# tracker2.net
KiCad netlist of a schematic drawn in EAGLE
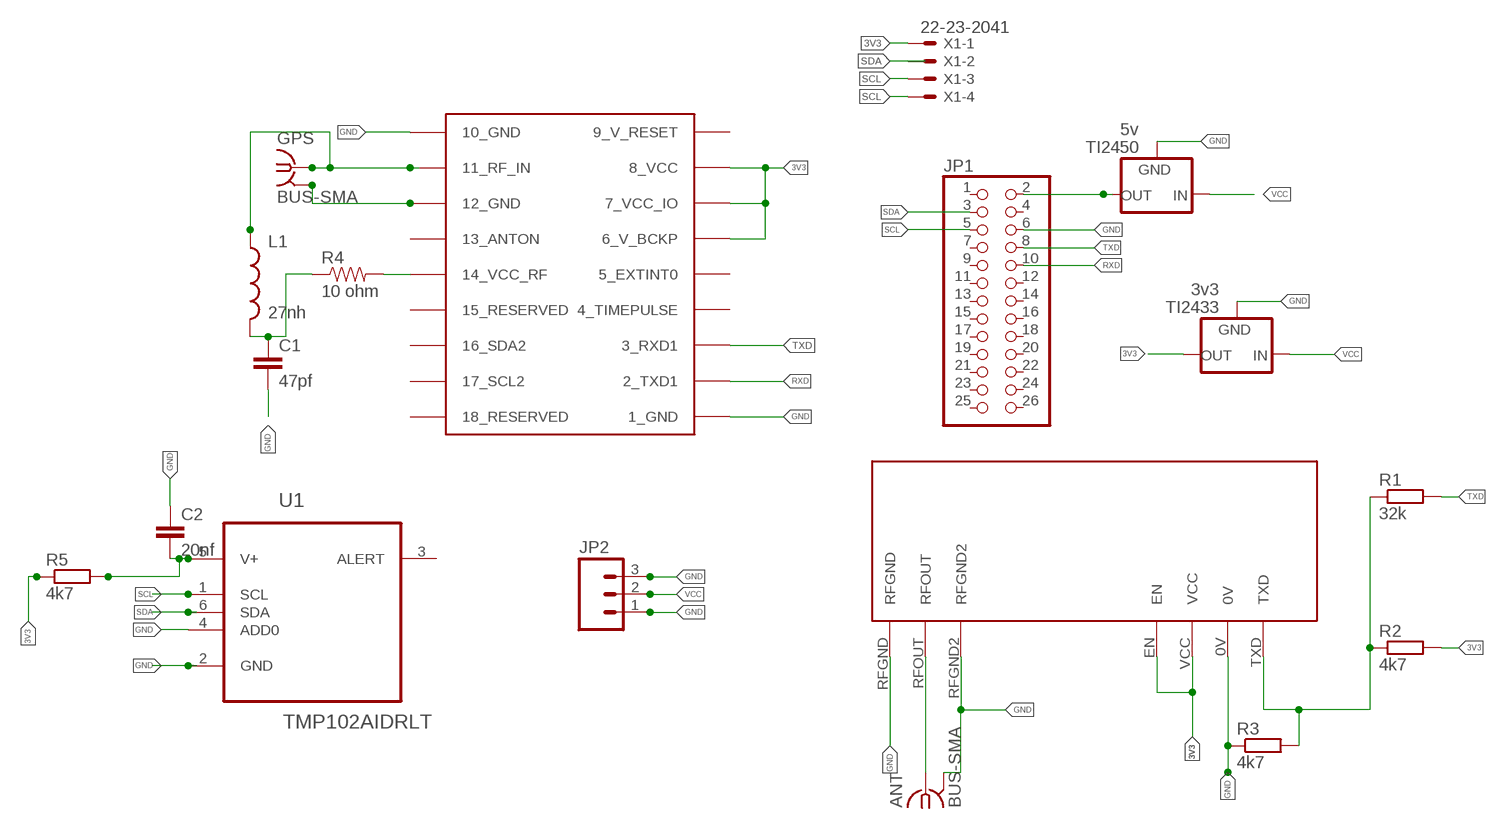
[diagram p0: schematic, sheet 1]

(export (version "E")
  (design (tool "Eeschema 10.0.6"))
  (components
    (comp (ref "ANT")
      (value "BUS-SMA")
      (footprint "eagle-import:BUS-SMA")
      (libsource (lib "eagle-import") (part "BUS-SMA"))
    )
    (comp (ref "C1")
      (value "47pf")
      (footprint "eagle-import:0603-CAP")
      (libsource (lib "eagle-import") (part "CAP0603-CAP"))
    )
    (comp (ref "C2")
      (value "20nf")
      (footprint "eagle-import:C0603")
      (libsource (lib "eagle-import") (part "C-EUC0603"))
    )
    (comp (ref "GPS")
      (value "BUS-SMA")
      (footprint "eagle-import:BUS-SMA")
      (libsource (lib "eagle-import") (part "BUS-SMA"))
    )
    (comp (ref "JP1")
      (value "PINHD-2X13")
      (footprint "eagle-import:2X13")
      (libsource (lib "eagle-import") (part "PINHD-2X13"))
    )
    (comp (ref "JP2")
      (value "M03PTH")
      (footprint "eagle-import:1X03")
      (libsource (lib "eagle-import") (part "M03PTH"))
    )
    (comp (ref "L1")
      (value "27nh")
      (footprint "eagle-import:0603")
      (libsource (lib "eagle-import") (part "INDUCTOR0603"))
    )
    (comp (ref "R1")
      (value "32k")
      (footprint "eagle-import:R0603")
      (libsource (lib "eagle-import") (part "R-EU_R0603"))
    )
    (comp (ref "R2")
      (value "4k7")
      (footprint "eagle-import:R0603")
      (libsource (lib "eagle-import") (part "R-EU_R0603"))
    )
    (comp (ref "R3")
      (value "4k7")
      (footprint "eagle-import:R0603")
      (libsource (lib "eagle-import") (part "R-EU_R0603"))
    )
    (comp (ref "R4")
      (value "10 ohm")
      (footprint "eagle-import:0603-RES")
      (libsource (lib "eagle-import") (part "RESISTOR0603"))
    )
    (comp (ref "R5")
      (value "4k7")
      (footprint "eagle-import:R0603")
      (libsource (lib "eagle-import") (part "R-EU_R0603"))
    )
    (comp (ref "TI2433")
      (value "3v3")
      (footprint "eagle-import:TO-220-ALT")
      (libsource (lib "eagle-import") (part "V_REG_78XX-TO-220"))
    )
    (comp (ref "TI2450")
      (value "5v")
      (footprint "eagle-import:TO-220-ALT")
      (libsource (lib "eagle-import") (part "V_REG_78XX-TO-220"))
    )
    (comp (ref "U$1")
      (value "NTX2")
      (footprint "eagle-import:NTX2")
      (libsource (lib "eagle-import") (part "NTX2"))
    )
    (comp (ref "U$2")
      (value "UBLOX_MAX")
      (footprint "eagle-import:UBLOX_MAX")
      (libsource (lib "eagle-import") (part "UBLOX_MAX"))
    )
    (comp (ref "U1")
      (value "TMP102AIDRLT")
      (footprint "eagle-import:SOT50P160X60-6N")
      (libsource (lib "eagle-import") (part "TMP102AIDRLT"))
    )
    (comp (ref "X1")
      (value "22-23-2041")
      (footprint "eagle-import:22-23-2041")
      (fields (field (name "MF") "MOLEX"))
      (libsource (lib "eagle-import") (part "22-23-2041"))
    )
  )
  (nets
    (net (code "1") (name "/9_V_RESET") (class "Default")
      (node (ref "U$2") (pin "9_V_RESET") (pinfunction "9_V_RESET_9_V_RESET") (pintype "power_in"))
    )
    (net (code "2") (name "3V3") (class "Default")
      (node (ref "C2") (pin "2") (pinfunction "2_2") (pintype "passive"))
      (node (ref "R2") (pin "2") (pinfunction "2_2") (pintype "passive"))
      (node (ref "R5") (pin "1") (pinfunction "1_1") (pintype "passive"))
      (node (ref "R5") (pin "2") (pinfunction "2_2") (pintype "passive"))
      (node (ref "TI2433") (pin "OUT") (pinfunction "OUT_OUT") (pintype "output"))
      (node (ref "U$1") (pin "EN") (pinfunction "EN_EN") (pintype "bidirectional"))
      (node (ref "U$1") (pin "VCC") (pinfunction "VCC_VCC") (pintype "bidirectional"))
      (node (ref "U$2") (pin "6_V_BCKP") (pinfunction "6_V_BCKP_6_V_BCKP") (pintype "bidirectional"))
      (node (ref "U$2") (pin "7_VCC_IO") (pinfunction "7_VCC_IO_7_VCC_IO") (pintype "power_in"))
      (node (ref "U$2") (pin "8_VCC") (pinfunction "8_VCC_8_VCC") (pintype "power_in"))
      (node (ref "U1") (pin "5") (pinfunction "V+_5") (pintype "power_in"))
      (node (ref "X1") (pin "1") (pinfunction "S_1") (pintype "passive"))
    )
    (net (code "3") (name "GND") (class "Default")
      (node (ref "ANT") (pin "2") (pinfunction "GND_2") (pintype "power_in"))
      (node (ref "ANT") (pin "3") (pinfunction "GND_3") (pintype "power_in"))
      (node (ref "ANT") (pin "4") (pinfunction "GND_4") (pintype "power_in"))
      (node (ref "ANT") (pin "5") (pinfunction "GND_5") (pintype "power_in"))
      (node (ref "C1") (pin "2") (pinfunction "2_2") (pintype "passive"))
      (node (ref "C2") (pin "1") (pinfunction "1_1") (pintype "passive"))
      (node (ref "GPS") (pin "2") (pinfunction "GND_2") (pintype "power_in"))
      (node (ref "GPS") (pin "3") (pinfunction "GND_3") (pintype "power_in"))
      (node (ref "GPS") (pin "4") (pinfunction "GND_4") (pintype "power_in"))
      (node (ref "GPS") (pin "5") (pinfunction "GND_5") (pintype "power_in"))
      (node (ref "JP1") (pin "6") (pinfunction "6_6") (pintype "passive"))
      (node (ref "JP2") (pin "1") (pinfunction "1_1") (pintype "passive"))
      (node (ref "JP2") (pin "3") (pinfunction "3_3") (pintype "passive"))
      (node (ref "R3") (pin "1") (pinfunction "1_1") (pintype "passive"))
      (node (ref "TI2433") (pin "GND") (pinfunction "GND_GND") (pintype "input"))
      (node (ref "TI2450") (pin "GND") (pinfunction "GND_GND") (pintype "input"))
      (node (ref "U$1") (pin "0V") (pinfunction "0V_0V") (pintype "bidirectional"))
      (node (ref "U$1") (pin "RFGND") (pinfunction "RFGND_RFGND") (pintype "bidirectional"))
      (node (ref "U$1") (pin "RFGND2") (pinfunction "RFGND2_RFGND2") (pintype "bidirectional"))
      (node (ref "U$2") (pin "10_GND") (pinfunction "10_GND_10_GND") (pintype "power_in"))
      (node (ref "U$2") (pin "12_GND") (pinfunction "12_GND_12_GND") (pintype "power_in"))
      (node (ref "U$2") (pin "1_GND") (pinfunction "1_GND_1_GND") (pintype "power_in"))
      (node (ref "U1") (pin "2") (pinfunction "GND_2") (pintype "passive"))
      (node (ref "U1") (pin "4") (pinfunction "ADD0_4") (pintype "input"))
      (node (ref "X1") (pin "4") (pinfunction "S_4") (pintype "passive"))
    )
    (net (code "4") (name "Net-(ANT-Pad1)") (class "Default")
      (node (ref "ANT") (pin "1") (pinfunction "1_1") (pintype "passive"))
      (node (ref "U$1") (pin "RFOUT") (pinfunction "RFOUT_RFOUT") (pintype "bidirectional"))
    )
    (net (code "5") (name "Net-(C1-Pad1)") (class "Default")
      (node (ref "C1") (pin "1") (pinfunction "1_1") (pintype "passive"))
      (node (ref "L1") (pin "2") (pinfunction "2_2") (pintype "passive"))
      (node (ref "R4") (pin "1") (pinfunction "1_1") (pintype "passive"))
    )
    (net (code "6") (name "Net-(GPS-Pad1)") (class "Default")
      (node (ref "GPS") (pin "1") (pinfunction "1_1") (pintype "passive"))
      (node (ref "L1") (pin "1") (pinfunction "1_1") (pintype "passive"))
      (node (ref "U$2") (pin "11_RF_IN") (pinfunction "11_RF_IN_11_RF_IN") (pintype "bidirectional"))
    )
    (net (code "7") (name "Net-(JP1-Pad2)") (class "Default")
      (node (ref "JP1") (pin "2") (pinfunction "2_2") (pintype "passive"))
      (node (ref "TI2450") (pin "OUT") (pinfunction "OUT_OUT") (pintype "output"))
    )
    (net (code "8") (name "Net-(R1-Pad1)") (class "Default")
      (node (ref "R1") (pin "1") (pinfunction "1_1") (pintype "passive"))
      (node (ref "R2") (pin "1") (pinfunction "1_1") (pintype "passive"))
      (node (ref "R3") (pin "2") (pinfunction "2_2") (pintype "passive"))
      (node (ref "U$1") (pin "TXD") (pinfunction "TXD_TXD") (pintype "bidirectional"))
    )
    (net (code "9") (name "Net-(R4-Pad2)") (class "Default")
      (node (ref "R4") (pin "2") (pinfunction "2_2") (pintype "passive"))
      (node (ref "U$2") (pin "14_VCC_RF") (pinfunction "14_VCC_RF_14_VCC_RF") (pintype "bidirectional"))
    )
    (net (code "10") (name "RXD") (class "Default")
      (node (ref "JP1") (pin "10") (pinfunction "10_10") (pintype "passive"))
      (node (ref "U$2") (pin "2_TXD1") (pinfunction "2_TXD1_2_TXD1") (pintype "bidirectional"))
    )
    (net (code "11") (name "SCL") (class "Default")
      (node (ref "JP1") (pin "5") (pinfunction "5_5") (pintype "passive"))
      (node (ref "U1") (pin "1") (pinfunction "SCL_1") (pintype "bidirectional"))
      (node (ref "X1") (pin "3") (pinfunction "S_3") (pintype "passive"))
    )
    (net (code "12") (name "SDA") (class "Default")
      (node (ref "JP1") (pin "3") (pinfunction "3_3") (pintype "passive"))
      (node (ref "U1") (pin "6") (pinfunction "SDA_6") (pintype "bidirectional"))
      (node (ref "X1") (pin "2") (pinfunction "S_2") (pintype "passive"))
    )
    (net (code "13") (name "TXD") (class "Default")
      (node (ref "JP1") (pin "8") (pinfunction "8_8") (pintype "passive"))
      (node (ref "R1") (pin "2") (pinfunction "2_2") (pintype "passive"))
      (node (ref "U$2") (pin "3_RXD1") (pinfunction "3_RXD1_3_RXD1") (pintype "bidirectional"))
    )
    (net (code "14") (name "VCC") (class "Default")
      (node (ref "JP2") (pin "2") (pinfunction "2_2") (pintype "passive"))
      (node (ref "TI2433") (pin "IN") (pinfunction "IN_IN") (pintype "input"))
      (node (ref "TI2450") (pin "IN") (pinfunction "IN_IN") (pintype "input"))
    )
    (net (code "15") (name "unconnected-(JP1-Pad1)") (class "Default")
      (node (ref "JP1") (pin "1") (pinfunction "1_1") (pintype "passive"))
    )
    (net (code "16") (name "unconnected-(JP1-Pad4)") (class "Default")
      (node (ref "JP1") (pin "4") (pinfunction "4_4") (pintype "passive"))
    )
    (net (code "17") (name "unconnected-(JP1-Pad7)") (class "Default")
      (node (ref "JP1") (pin "7") (pinfunction "7_7") (pintype "passive"))
    )
    (net (code "18") (name "unconnected-(JP1-Pad9)") (class "Default")
      (node (ref "JP1") (pin "9") (pinfunction "9_9") (pintype "passive"))
    )
    (net (code "19") (name "unconnected-(JP1-Pad11)") (class "Default")
      (node (ref "JP1") (pin "11") (pinfunction "11_11") (pintype "passive"))
    )
    (net (code "20") (name "unconnected-(JP1-Pad12)") (class "Default")
      (node (ref "JP1") (pin "12") (pinfunction "12_12") (pintype "passive"))
    )
    (net (code "21") (name "unconnected-(JP1-Pad13)") (class "Default")
      (node (ref "JP1") (pin "13") (pinfunction "13_13") (pintype "passive"))
    )
    (net (code "22") (name "unconnected-(JP1-Pad14)") (class "Default")
      (node (ref "JP1") (pin "14") (pinfunction "14_14") (pintype "passive"))
    )
    (net (code "23") (name "unconnected-(JP1-Pad15)") (class "Default")
      (node (ref "JP1") (pin "15") (pinfunction "15_15") (pintype "passive"))
    )
    (net (code "24") (name "unconnected-(JP1-Pad16)") (class "Default")
      (node (ref "JP1") (pin "16") (pinfunction "16_16") (pintype "passive"))
    )
    (net (code "25") (name "unconnected-(JP1-Pad17)") (class "Default")
      (node (ref "JP1") (pin "17") (pinfunction "17_17") (pintype "passive"))
    )
    (net (code "26") (name "unconnected-(JP1-Pad18)") (class "Default")
      (node (ref "JP1") (pin "18") (pinfunction "18_18") (pintype "passive"))
    )
    (net (code "27") (name "unconnected-(JP1-Pad19)") (class "Default")
      (node (ref "JP1") (pin "19") (pinfunction "19_19") (pintype "passive"))
    )
    (net (code "28") (name "unconnected-(JP1-Pad20)") (class "Default")
      (node (ref "JP1") (pin "20") (pinfunction "20_20") (pintype "passive"))
    )
    (net (code "29") (name "unconnected-(JP1-Pad21)") (class "Default")
      (node (ref "JP1") (pin "21") (pinfunction "21_21") (pintype "passive"))
    )
    (net (code "30") (name "unconnected-(JP1-Pad22)") (class "Default")
      (node (ref "JP1") (pin "22") (pinfunction "22_22") (pintype "passive"))
    )
    (net (code "31") (name "unconnected-(JP1-Pad23)") (class "Default")
      (node (ref "JP1") (pin "23") (pinfunction "23_23") (pintype "passive"))
    )
    (net (code "32") (name "unconnected-(JP1-Pad24)") (class "Default")
      (node (ref "JP1") (pin "24") (pinfunction "24_24") (pintype "passive"))
    )
    (net (code "33") (name "unconnected-(JP1-Pad25)") (class "Default")
      (node (ref "JP1") (pin "25") (pinfunction "25_25") (pintype "passive"))
    )
    (net (code "34") (name "unconnected-(JP1-Pad26)") (class "Default")
      (node (ref "JP1") (pin "26") (pinfunction "26_26") (pintype "passive"))
    )
    (net (code "35") (name "unconnected-(U$2-Pad4_TIMEPULSE)") (class "Default")
      (node (ref "U$2") (pin "4_TIMEPULSE") (pinfunction "4_TIMEPULSE_4_TIMEPULSE") (pintype "bidirectional"))
    )
    (net (code "36") (name "unconnected-(U$2-Pad5_EXTINT0)") (class "Default")
      (node (ref "U$2") (pin "5_EXTINT0") (pinfunction "5_EXTINT0_5_EXTINT0") (pintype "bidirectional"))
    )
    (net (code "37") (name "unconnected-(U$2-Pad13_ANTON)") (class "Default")
      (node (ref "U$2") (pin "13_ANTON") (pinfunction "13_ANTON_13_ANTON") (pintype "bidirectional"))
    )
    (net (code "38") (name "unconnected-(U$2-Pad15_RESERVED)") (class "Default")
      (node (ref "U$2") (pin "15_RESERVED") (pinfunction "15_RESERVED_15_RESERVED") (pintype "bidirectional"))
    )
    (net (code "39") (name "unconnected-(U$2-Pad16_SDA2)") (class "Default")
      (node (ref "U$2") (pin "16_SDA2") (pinfunction "16_SDA2_16_SDA2") (pintype "bidirectional"))
    )
    (net (code "40") (name "unconnected-(U$2-Pad17_SCL2)") (class "Default")
      (node (ref "U$2") (pin "17_SCL2") (pinfunction "17_SCL2_17_SCL2") (pintype "bidirectional"))
    )
    (net (code "41") (name "unconnected-(U$2-Pad18_RESERVED)") (class "Default")
      (node (ref "U$2") (pin "18_RESERVED") (pinfunction "18_RESERVED_18_RESERVED") (pintype "bidirectional"))
    )
    (net (code "42") (name "unconnected-(U1-ALERT-Pad3)") (class "Default")
      (node (ref "U1") (pin "3") (pinfunction "ALERT_3") (pintype "output"))
    )
  )
)
